# 5_AnalogChannels_1_2_3_4.net
KiCad netlist of a schematic drawn in Altium Designer
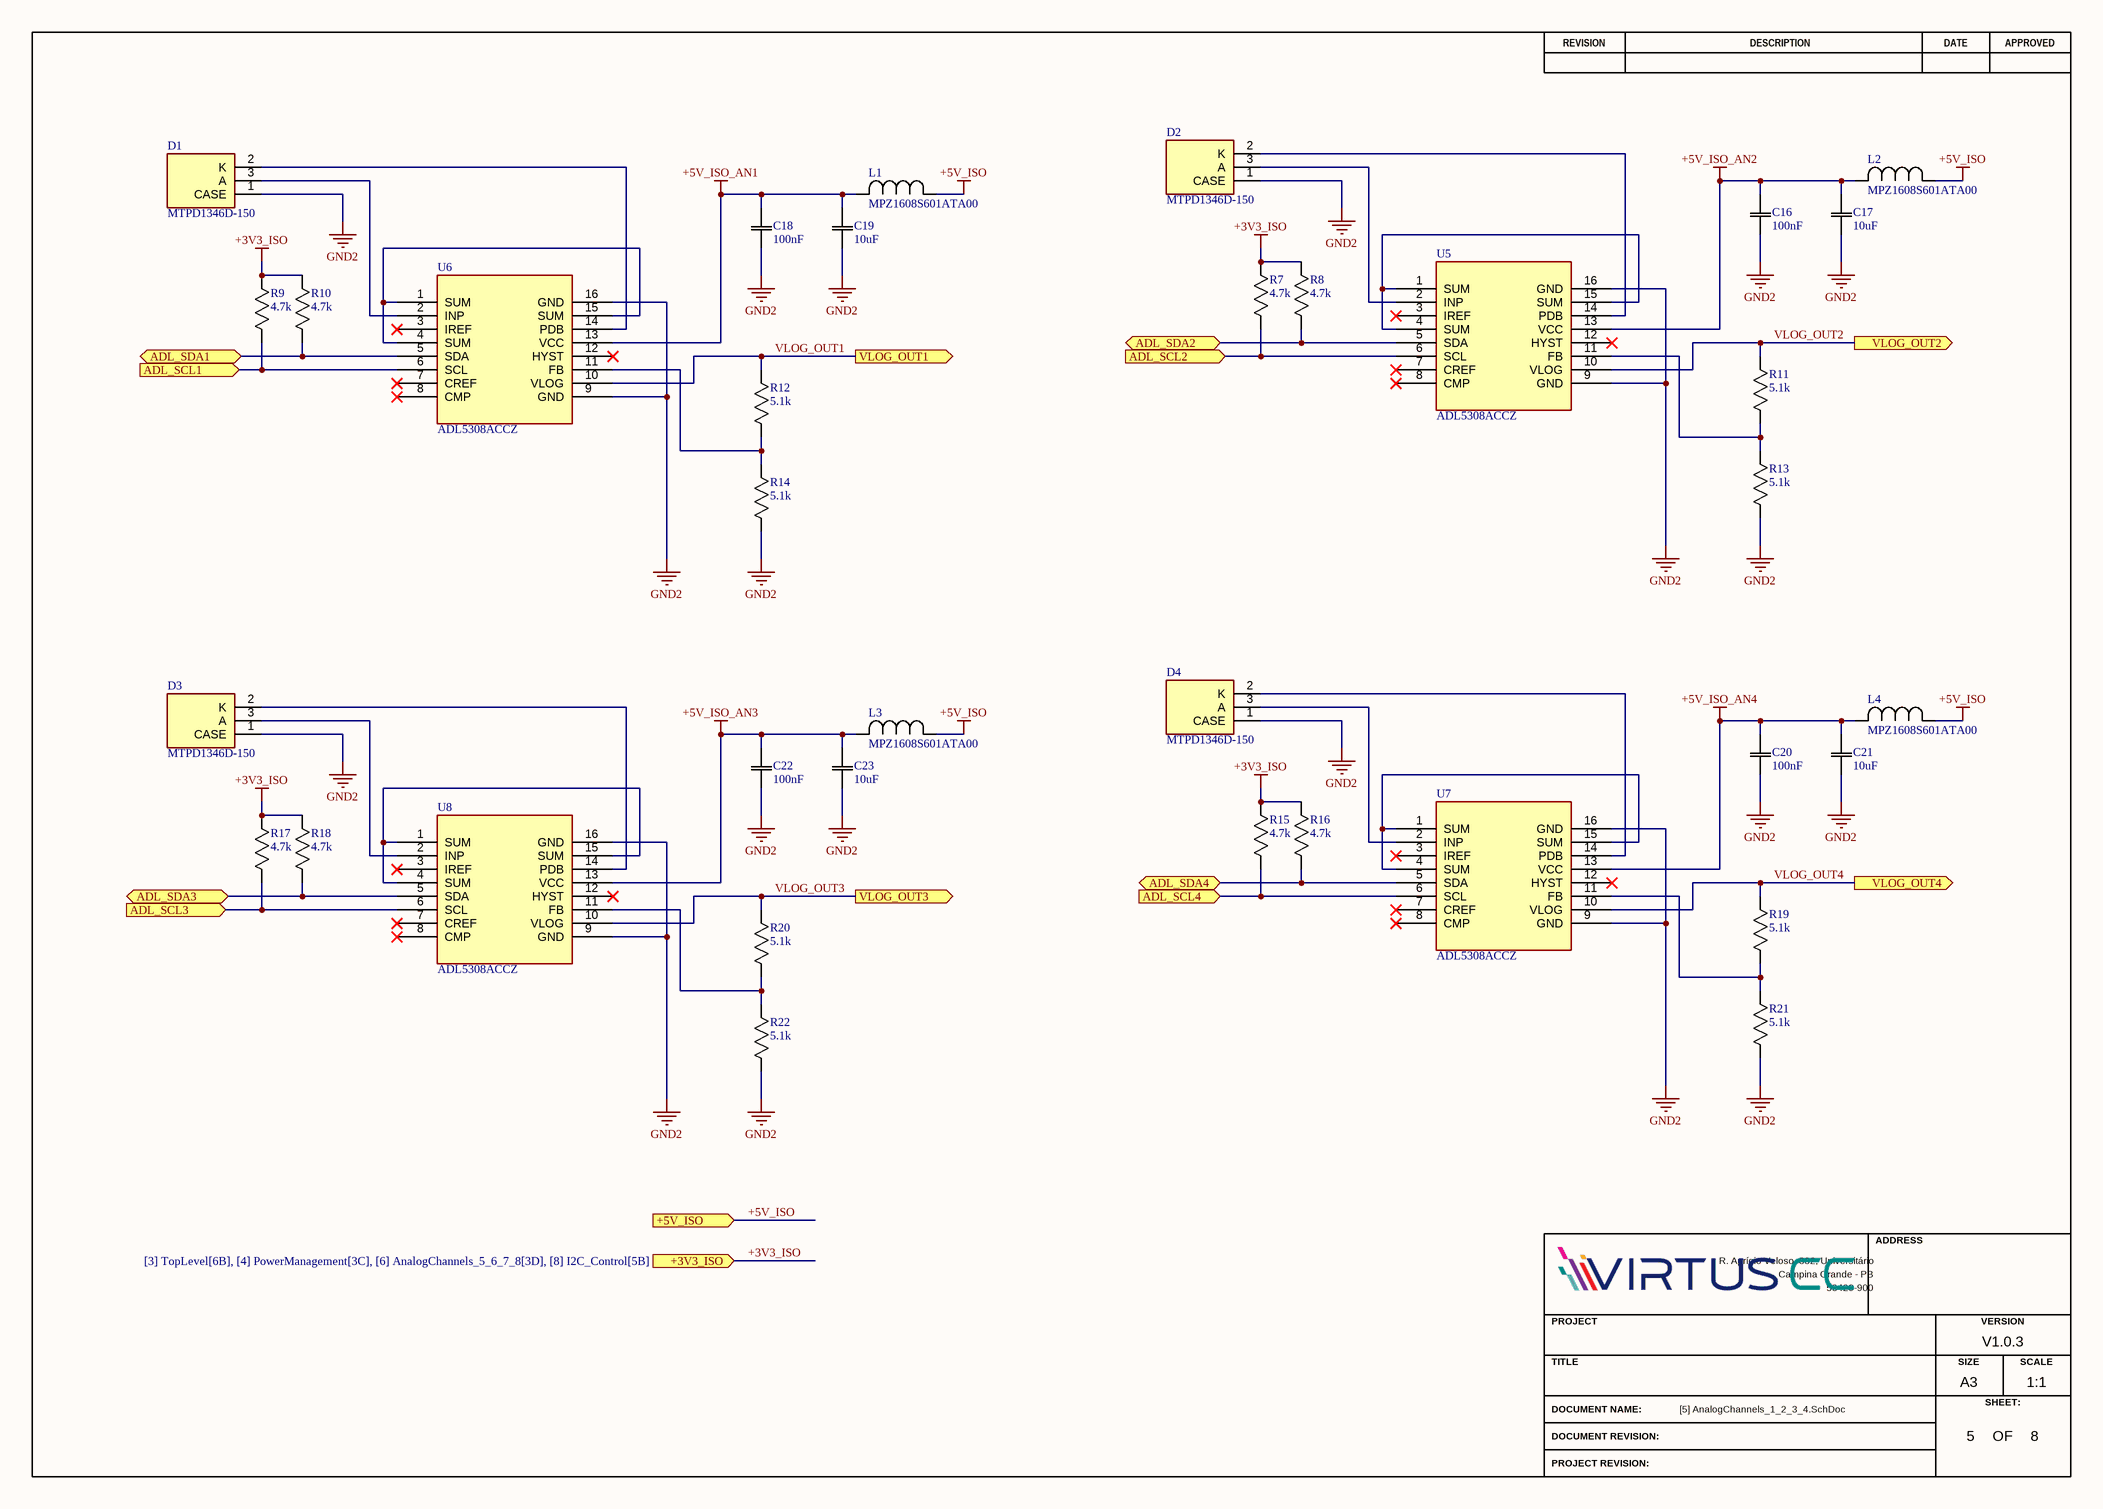
[diagram p0: [5] AnalogChannels_1_2_3_4.SchDoc]

(export (version "E")
  (design (tool "Eeschema 10.0.6"))
  (components
    (comp (ref "C16")
      (value "100nF")
      (footprint "CAPC1005X40N")
      (description "0.1 µF ±10% 50V Ceramic Capacitor X7R 0402 (1005 Metric)")
      (fields
        (field (name "MANUFACTURER_PART_NUMBER") "GCM155R71H104KE02D")
        (field (name "COPYRIGHT") "Copyright (C) 2026 Ultra Librarian. All rights reserved.")
      )
      (libsource (lib "PCEIOT") (part "GCM155R71H104KE02D"))
    )
    (comp (ref "C17")
      (value "10uF")
      (footprint "CAPC1005X40N")
      (description "10 µF ±20% 10V Ceramic Capacitor X5R 0402 (1005 Metric)")
      (fields
        (field (name "MANUFACTURER_PART_NUMBER") "GRT155R61A106ME13D")
        (field (name "COPYRIGHT") "Copyright (C) 2026 Ultra Librarian. All rights reserved.")
      )
      (libsource (lib "PCEIOT") (part "GRT155R61A106ME13D"))
    )
    (comp (ref "C18")
      (value "100nF")
      (footprint "CAPC1005X40N")
      (description "0.1 µF ±10% 50V Ceramic Capacitor X7R 0402 (1005 Metric)")
      (fields
        (field (name "MANUFACTURER_PART_NUMBER") "GCM155R71H104KE02D")
        (field (name "COPYRIGHT") "Copyright (C) 2026 Ultra Librarian. All rights reserved.")
      )
      (libsource (lib "PCEIOT") (part "GCM155R71H104KE02D"))
    )
    (comp (ref "C19")
      (value "10uF")
      (footprint "CAPC1005X40N")
      (description "10 µF ±20% 10V Ceramic Capacitor X5R 0402 (1005 Metric)")
      (fields
        (field (name "MANUFACTURER_PART_NUMBER") "GRT155R61A106ME13D")
        (field (name "COPYRIGHT") "Copyright (C) 2026 Ultra Librarian. All rights reserved.")
      )
      (libsource (lib "PCEIOT") (part "GRT155R61A106ME13D"))
    )
    (comp (ref "C20")
      (value "100nF")
      (footprint "CAPC1005X40N")
      (description "0.1 µF ±10% 50V Ceramic Capacitor X7R 0402 (1005 Metric)")
      (fields
        (field (name "MANUFACTURER_PART_NUMBER") "GCM155R71H104KE02D")
        (field (name "COPYRIGHT") "Copyright (C) 2026 Ultra Librarian. All rights reserved.")
      )
      (libsource (lib "PCEIOT") (part "GCM155R71H104KE02D"))
    )
    (comp (ref "C21")
      (value "10uF")
      (footprint "CAPC1005X40N")
      (description "10 µF ±20% 10V Ceramic Capacitor X5R 0402 (1005 Metric)")
      (fields
        (field (name "MANUFACTURER_PART_NUMBER") "GRT155R61A106ME13D")
        (field (name "COPYRIGHT") "Copyright (C) 2026 Ultra Librarian. All rights reserved.")
      )
      (libsource (lib "PCEIOT") (part "GRT155R61A106ME13D"))
    )
    (comp (ref "C22")
      (value "100nF")
      (footprint "CAPC1005X40N")
      (description "0.1 µF ±10% 50V Ceramic Capacitor X7R 0402 (1005 Metric)")
      (fields
        (field (name "MANUFACTURER_PART_NUMBER") "GCM155R71H104KE02D")
        (field (name "COPYRIGHT") "Copyright (C) 2026 Ultra Librarian. All rights reserved.")
      )
      (libsource (lib "PCEIOT") (part "GCM155R71H104KE02D"))
    )
    (comp (ref "C23")
      (value "10uF")
      (footprint "CAPC1005X40N")
      (description "10 µF ±20% 10V Ceramic Capacitor X5R 0402 (1005 Metric)")
      (fields
        (field (name "MANUFACTURER_PART_NUMBER") "GRT155R61A106ME13D")
        (field (name "COPYRIGHT") "Copyright (C) 2026 Ultra Librarian. All rights reserved.")
      )
      (libsource (lib "PCEIOT") (part "GRT155R61A106ME13D"))
    )
    (comp (ref "D1")
      (value "MTPD1346D-150")
      (footprint "TO127P540X1680-3N")
      (description "Photodiode 1300nm TO-46-3 Lens Top Metal Can")
      (libsource (lib "PCEIOT") (part "MTPD1346D-150"))
    )
    (comp (ref "D2")
      (value "MTPD1346D-150")
      (footprint "TO127P540X1680-3N")
      (description "Photodiode 1300nm TO-46-3 Lens Top Metal Can")
      (libsource (lib "PCEIOT") (part "MTPD1346D-150"))
    )
    (comp (ref "D3")
      (value "MTPD1346D-150")
      (footprint "TO127P540X1680-3N")
      (description "Photodiode 1300nm TO-46-3 Lens Top Metal Can")
      (libsource (lib "PCEIOT") (part "MTPD1346D-150"))
    )
    (comp (ref "D4")
      (value "MTPD1346D-150")
      (footprint "TO127P540X1680-3N")
      (description "Photodiode 1300nm TO-46-3 Lens Top Metal Can")
      (libsource (lib "PCEIOT") (part "MTPD1346D-150"))
    )
    (comp (ref "L1")
      (value "MPZ1608S601ATA00")
      (footprint "INDC1608X06N")
      (description "INDUCTOR; SMT (0603); FERRITE-BEAD; 600; TOL=+/-25%; 1A; -55 DEGC TO +125 DEGC")
      (fields (field (name "COPYRIGHT") "Copyright (C) 2026 Ultra Librarian. All rights reserved."))
      (libsource (lib "PCEIOT") (part "MPZ1608S601ATA00"))
    )
    (comp (ref "L2")
      (value "MPZ1608S601ATA00")
      (footprint "INDC1608X06N")
      (description "INDUCTOR; SMT (0603); FERRITE-BEAD; 600; TOL=+/-25%; 1A; -55 DEGC TO +125 DEGC")
      (fields (field (name "COPYRIGHT") "Copyright (C) 2026 Ultra Librarian. All rights reserved."))
      (libsource (lib "PCEIOT") (part "MPZ1608S601ATA00"))
    )
    (comp (ref "L3")
      (value "MPZ1608S601ATA00")
      (footprint "INDC1608X06N")
      (description "INDUCTOR; SMT (0603); FERRITE-BEAD; 600; TOL=+/-25%; 1A; -55 DEGC TO +125 DEGC")
      (fields (field (name "COPYRIGHT") "Copyright (C) 2026 Ultra Librarian. All rights reserved."))
      (libsource (lib "PCEIOT") (part "MPZ1608S601ATA00"))
    )
    (comp (ref "L4")
      (value "MPZ1608S601ATA00")
      (footprint "INDC1608X06N")
      (description "INDUCTOR; SMT (0603); FERRITE-BEAD; 600; TOL=+/-25%; 1A; -55 DEGC TO +125 DEGC")
      (fields (field (name "COPYRIGHT") "Copyright (C) 2026 Ultra Librarian. All rights reserved."))
      (libsource (lib "PCEIOT") (part "MPZ1608S601ATA00"))
    )
    (comp (ref "R7")
      (value "4.7k")
      (footprint "RESC1005X40N")
      (description "4.7 kOhms ±1% 0.063W, 1/16W Chip Resistor 0402 (1005 Metric) Moisture Resistant Thick Film")
      (fields
        (field (name "MANUFACTURER_PART_NUMBER") "RC0402FR-074K7L")
        (field (name "COPYRIGHT") "Copyright (C) 2025 Ultra Librarian. All rights reserved.")
      )
      (libsource (lib "PCEIOT") (part "RC0402FR-074K7L"))
    )
    (comp (ref "R8")
      (value "4.7k")
      (footprint "RESC1005X40N")
      (description "4.7 kOhms ±1% 0.063W, 1/16W Chip Resistor 0402 (1005 Metric) Moisture Resistant Thick Film")
      (fields
        (field (name "MANUFACTURER_PART_NUMBER") "RC0402FR-074K7L")
        (field (name "COPYRIGHT") "Copyright (C) 2025 Ultra Librarian. All rights reserved.")
      )
      (libsource (lib "PCEIOT") (part "RC0402FR-074K7L"))
    )
    (comp (ref "R9")
      (value "4.7k")
      (footprint "RESC1005X40N")
      (description "4.7 kOhms ±1% 0.063W, 1/16W Chip Resistor 0402 (1005 Metric) Moisture Resistant Thick Film")
      (fields
        (field (name "MANUFACTURER_PART_NUMBER") "RC0402FR-074K7L")
        (field (name "COPYRIGHT") "Copyright (C) 2025 Ultra Librarian. All rights reserved.")
      )
      (libsource (lib "PCEIOT") (part "RC0402FR-074K7L"))
    )
    (comp (ref "R10")
      (value "4.7k")
      (footprint "RESC1005X40N")
      (description "4.7 kOhms ±1% 0.063W, 1/16W Chip Resistor 0402 (1005 Metric) Moisture Resistant Thick Film")
      (fields
        (field (name "MANUFACTURER_PART_NUMBER") "RC0402FR-074K7L")
        (field (name "COPYRIGHT") "Copyright (C) 2025 Ultra Librarian. All rights reserved.")
      )
      (libsource (lib "PCEIOT") (part "RC0402FR-074K7L"))
    )
    (comp (ref "R11")
      (value "5.1k")
      (footprint "RESC1005X40N")
      (description "5.1 kOhms ±1% 0.063W, 1/16W Chip Resistor 0402 (1005 Metric) Moisture Resistant Thick Film")
      (fields
        (field (name "MANUFACTURER_PART_NUMBER") "RC0402FR-075K1L")
        (field (name "COPYRIGHT") "Copyright (C) 2025 Ultra Librarian. All rights reserved.")
      )
      (libsource (lib "PCEIOT") (part "RC0402FR-075K1L"))
    )
    (comp (ref "R12")
      (value "5.1k")
      (footprint "RESC1005X40N")
      (description "5.1 kOhms ±1% 0.063W, 1/16W Chip Resistor 0402 (1005 Metric) Moisture Resistant Thick Film")
      (fields
        (field (name "MANUFACTURER_PART_NUMBER") "RC0402FR-075K1L")
        (field (name "COPYRIGHT") "Copyright (C) 2025 Ultra Librarian. All rights reserved.")
      )
      (libsource (lib "PCEIOT") (part "RC0402FR-075K1L"))
    )
    (comp (ref "R13")
      (value "5.1k")
      (footprint "RESC1005X40N")
      (description "5.1 kOhms ±1% 0.063W, 1/16W Chip Resistor 0402 (1005 Metric) Moisture Resistant Thick Film")
      (fields
        (field (name "MANUFACTURER_PART_NUMBER") "RC0402FR-075K1L")
        (field (name "COPYRIGHT") "Copyright (C) 2025 Ultra Librarian. All rights reserved.")
      )
      (libsource (lib "PCEIOT") (part "RC0402FR-075K1L"))
    )
    (comp (ref "R14")
      (value "5.1k")
      (footprint "RESC1005X40N")
      (description "5.1 kOhms ±1% 0.063W, 1/16W Chip Resistor 0402 (1005 Metric) Moisture Resistant Thick Film")
      (fields
        (field (name "MANUFACTURER_PART_NUMBER") "RC0402FR-075K1L")
        (field (name "COPYRIGHT") "Copyright (C) 2025 Ultra Librarian. All rights reserved.")
      )
      (libsource (lib "PCEIOT") (part "RC0402FR-075K1L"))
    )
    (comp (ref "R15")
      (value "4.7k")
      (footprint "RESC1005X40N")
      (description "4.7 kOhms ±1% 0.063W, 1/16W Chip Resistor 0402 (1005 Metric) Moisture Resistant Thick Film")
      (fields
        (field (name "MANUFACTURER_PART_NUMBER") "RC0402FR-074K7L")
        (field (name "COPYRIGHT") "Copyright (C) 2025 Ultra Librarian. All rights reserved.")
      )
      (libsource (lib "PCEIOT") (part "RC0402FR-074K7L"))
    )
    (comp (ref "R16")
      (value "4.7k")
      (footprint "RESC1005X40N")
      (description "4.7 kOhms ±1% 0.063W, 1/16W Chip Resistor 0402 (1005 Metric) Moisture Resistant Thick Film")
      (fields
        (field (name "MANUFACTURER_PART_NUMBER") "RC0402FR-074K7L")
        (field (name "COPYRIGHT") "Copyright (C) 2025 Ultra Librarian. All rights reserved.")
      )
      (libsource (lib "PCEIOT") (part "RC0402FR-074K7L"))
    )
    (comp (ref "R17")
      (value "4.7k")
      (footprint "RESC1005X40N")
      (description "4.7 kOhms ±1% 0.063W, 1/16W Chip Resistor 0402 (1005 Metric) Moisture Resistant Thick Film")
      (fields
        (field (name "MANUFACTURER_PART_NUMBER") "RC0402FR-074K7L")
        (field (name "COPYRIGHT") "Copyright (C) 2025 Ultra Librarian. All rights reserved.")
      )
      (libsource (lib "PCEIOT") (part "RC0402FR-074K7L"))
    )
    (comp (ref "R18")
      (value "4.7k")
      (footprint "RESC1005X40N")
      (description "4.7 kOhms ±1% 0.063W, 1/16W Chip Resistor 0402 (1005 Metric) Moisture Resistant Thick Film")
      (fields
        (field (name "MANUFACTURER_PART_NUMBER") "RC0402FR-074K7L")
        (field (name "COPYRIGHT") "Copyright (C) 2025 Ultra Librarian. All rights reserved.")
      )
      (libsource (lib "PCEIOT") (part "RC0402FR-074K7L"))
    )
    (comp (ref "R19")
      (value "5.1k")
      (footprint "RESC1005X40N")
      (description "5.1 kOhms ±1% 0.063W, 1/16W Chip Resistor 0402 (1005 Metric) Moisture Resistant Thick Film")
      (fields
        (field (name "MANUFACTURER_PART_NUMBER") "RC0402FR-075K1L")
        (field (name "COPYRIGHT") "Copyright (C) 2025 Ultra Librarian. All rights reserved.")
      )
      (libsource (lib "PCEIOT") (part "RC0402FR-075K1L"))
    )
    (comp (ref "R20")
      (value "5.1k")
      (footprint "RESC1005X40N")
      (description "5.1 kOhms ±1% 0.063W, 1/16W Chip Resistor 0402 (1005 Metric) Moisture Resistant Thick Film")
      (fields
        (field (name "MANUFACTURER_PART_NUMBER") "RC0402FR-075K1L")
        (field (name "COPYRIGHT") "Copyright (C) 2025 Ultra Librarian. All rights reserved.")
      )
      (libsource (lib "PCEIOT") (part "RC0402FR-075K1L"))
    )
    (comp (ref "R21")
      (value "5.1k")
      (footprint "RESC1005X40N")
      (description "5.1 kOhms ±1% 0.063W, 1/16W Chip Resistor 0402 (1005 Metric) Moisture Resistant Thick Film")
      (fields
        (field (name "MANUFACTURER_PART_NUMBER") "RC0402FR-075K1L")
        (field (name "COPYRIGHT") "Copyright (C) 2025 Ultra Librarian. All rights reserved.")
      )
      (libsource (lib "PCEIOT") (part "RC0402FR-075K1L"))
    )
    (comp (ref "R22")
      (value "5.1k")
      (footprint "RESC1005X40N")
      (description "5.1 kOhms ±1% 0.063W, 1/16W Chip Resistor 0402 (1005 Metric) Moisture Resistant Thick Film")
      (fields
        (field (name "MANUFACTURER_PART_NUMBER") "RC0402FR-075K1L")
        (field (name "COPYRIGHT") "Copyright (C) 2025 Ultra Librarian. All rights reserved.")
      )
      (libsource (lib "PCEIOT") (part "RC0402FR-075K1L"))
    )
    (comp (ref "U5")
      (value "ADL5308ACCZ")
      (footprint "CC-14-4_ADI")
      (description "Logarithmic Converter, 105Deg C, Lga-Ep Rohs Compliant: Yes ¦Analog Devices, Inc. ADL5308ACCZ")
      (libsource (lib "PCEIOT") (part "ADL5308ACCZ"))
    )
    (comp (ref "U6")
      (value "ADL5308ACCZ")
      (footprint "CC-14-4_ADI")
      (description "Logarithmic Converter, 105Deg C, Lga-Ep Rohs Compliant: Yes ¦Analog Devices, Inc. ADL5308ACCZ")
      (libsource (lib "PCEIOT") (part "ADL5308ACCZ"))
    )
    (comp (ref "U7")
      (value "ADL5308ACCZ")
      (footprint "CC-14-4_ADI")
      (description "Logarithmic Converter, 105Deg C, Lga-Ep Rohs Compliant: Yes ¦Analog Devices, Inc. ADL5308ACCZ")
      (libsource (lib "PCEIOT") (part "ADL5308ACCZ"))
    )
    (comp (ref "U8")
      (value "ADL5308ACCZ")
      (footprint "CC-14-4_ADI")
      (description "Logarithmic Converter, 105Deg C, Lga-Ep Rohs Compliant: Yes ¦Analog Devices, Inc. ADL5308ACCZ")
      (libsource (lib "PCEIOT") (part "ADL5308ACCZ"))
    )
  )
  (nets
    (net (code "1") (name "+3V3_ISO") (class "Default")
      (node (ref "R10") (pin "1") (pinfunction "1_1") (pintype "passive"))
      (node (ref "R15") (pin "1") (pinfunction "1_1") (pintype "passive"))
      (node (ref "R16") (pin "1") (pinfunction "1_1") (pintype "passive"))
      (node (ref "R17") (pin "1") (pinfunction "1_1") (pintype "passive"))
      (node (ref "R18") (pin "1") (pinfunction "1_1") (pintype "passive"))
      (node (ref "R7") (pin "1") (pinfunction "1_1") (pintype "passive"))
      (node (ref "R8") (pin "1") (pinfunction "1_1") (pintype "passive"))
      (node (ref "R9") (pin "1") (pinfunction "1_1") (pintype "passive"))
    )
    (net (code "2") (name "+5V_ISO") (class "Default")
      (node (ref "L1") (pin "1") (pinfunction "1_1") (pintype "passive"))
      (node (ref "L2") (pin "1") (pinfunction "1_1") (pintype "passive"))
      (node (ref "L3") (pin "1") (pinfunction "1_1") (pintype "passive"))
      (node (ref "L4") (pin "1") (pinfunction "1_1") (pintype "passive"))
    )
    (net (code "3") (name "+5V_ISO_AN1") (class "Default")
      (node (ref "C18") (pin "2") (pinfunction "2_2") (pintype "passive"))
      (node (ref "C19") (pin "2") (pinfunction "2_2") (pintype "passive"))
      (node (ref "L1") (pin "2") (pinfunction "2_2") (pintype "passive"))
      (node (ref "U6") (pin "13") (pinfunction "VCC_13") (pintype "passive"))
    )
    (net (code "4") (name "+5V_ISO_AN2") (class "Default")
      (node (ref "C16") (pin "2") (pinfunction "2_2") (pintype "passive"))
      (node (ref "C17") (pin "2") (pinfunction "2_2") (pintype "passive"))
      (node (ref "L2") (pin "2") (pinfunction "2_2") (pintype "passive"))
      (node (ref "U5") (pin "13") (pinfunction "VCC_13") (pintype "passive"))
    )
    (net (code "5") (name "+5V_ISO_AN3") (class "Default")
      (node (ref "C22") (pin "2") (pinfunction "2_2") (pintype "passive"))
      (node (ref "C23") (pin "2") (pinfunction "2_2") (pintype "passive"))
      (node (ref "L3") (pin "2") (pinfunction "2_2") (pintype "passive"))
      (node (ref "U8") (pin "13") (pinfunction "VCC_13") (pintype "passive"))
    )
    (net (code "6") (name "+5V_ISO_AN4") (class "Default")
      (node (ref "C20") (pin "2") (pinfunction "2_2") (pintype "passive"))
      (node (ref "C21") (pin "2") (pinfunction "2_2") (pintype "passive"))
      (node (ref "L4") (pin "2") (pinfunction "2_2") (pintype "passive"))
      (node (ref "U7") (pin "13") (pinfunction "VCC_13") (pintype "passive"))
    )
    (net (code "7") (name "/ADL_SCL1") (class "Default")
      (node (ref "R9") (pin "2") (pinfunction "2_2") (pintype "passive"))
      (node (ref "U6") (pin "6") (pinfunction "SCL_6") (pintype "passive"))
    )
    (net (code "8") (name "/ADL_SCL2") (class "Default")
      (node (ref "R7") (pin "2") (pinfunction "2_2") (pintype "passive"))
      (node (ref "U5") (pin "6") (pinfunction "SCL_6") (pintype "passive"))
    )
    (net (code "9") (name "/ADL_SCL3") (class "Default")
      (node (ref "R17") (pin "2") (pinfunction "2_2") (pintype "passive"))
      (node (ref "U8") (pin "6") (pinfunction "SCL_6") (pintype "passive"))
    )
    (net (code "10") (name "/ADL_SCL4") (class "Default")
      (node (ref "R15") (pin "2") (pinfunction "2_2") (pintype "passive"))
      (node (ref "U7") (pin "6") (pinfunction "SCL_6") (pintype "passive"))
    )
    (net (code "11") (name "/ADL_SDA1") (class "Default")
      (node (ref "R10") (pin "2") (pinfunction "2_2") (pintype "passive"))
      (node (ref "U6") (pin "5") (pinfunction "SDA_5") (pintype "passive"))
    )
    (net (code "12") (name "/ADL_SDA2") (class "Default")
      (node (ref "R8") (pin "2") (pinfunction "2_2") (pintype "passive"))
      (node (ref "U5") (pin "5") (pinfunction "SDA_5") (pintype "passive"))
    )
    (net (code "13") (name "/ADL_SDA3") (class "Default")
      (node (ref "R18") (pin "2") (pinfunction "2_2") (pintype "passive"))
      (node (ref "U8") (pin "5") (pinfunction "SDA_5") (pintype "passive"))
    )
    (net (code "14") (name "/ADL_SDA4") (class "Default")
      (node (ref "R16") (pin "2") (pinfunction "2_2") (pintype "passive"))
      (node (ref "U7") (pin "5") (pinfunction "SDA_5") (pintype "passive"))
    )
    (net (code "15") (name "/VLOG_OUT1") (class "Default")
      (node (ref "R12") (pin "1") (pinfunction "1_1") (pintype "passive"))
      (node (ref "U6") (pin "10") (pinfunction "VLOG_10") (pintype "passive"))
    )
    (net (code "16") (name "/VLOG_OUT2") (class "Default")
      (node (ref "R11") (pin "1") (pinfunction "1_1") (pintype "passive"))
      (node (ref "U5") (pin "10") (pinfunction "VLOG_10") (pintype "passive"))
    )
    (net (code "17") (name "/VLOG_OUT3") (class "Default")
      (node (ref "R20") (pin "1") (pinfunction "1_1") (pintype "passive"))
      (node (ref "U8") (pin "10") (pinfunction "VLOG_10") (pintype "passive"))
    )
    (net (code "18") (name "/VLOG_OUT4") (class "Default")
      (node (ref "R19") (pin "1") (pinfunction "1_1") (pintype "passive"))
      (node (ref "U7") (pin "10") (pinfunction "VLOG_10") (pintype "passive"))
    )
    (net (code "19") (name "GND2") (class "Default")
      (node (ref "C16") (pin "1") (pinfunction "1_1") (pintype "passive"))
      (node (ref "C17") (pin "1") (pinfunction "1_1") (pintype "passive"))
      (node (ref "C18") (pin "1") (pinfunction "1_1") (pintype "passive"))
      (node (ref "C19") (pin "1") (pinfunction "1_1") (pintype "passive"))
      (node (ref "C20") (pin "1") (pinfunction "1_1") (pintype "passive"))
      (node (ref "C21") (pin "1") (pinfunction "1_1") (pintype "passive"))
      (node (ref "C22") (pin "1") (pinfunction "1_1") (pintype "passive"))
      (node (ref "C23") (pin "1") (pinfunction "1_1") (pintype "passive"))
      (node (ref "D1") (pin "1") (pinfunction "CASE_1") (pintype "passive"))
      (node (ref "D2") (pin "1") (pinfunction "CASE_1") (pintype "passive"))
      (node (ref "D3") (pin "1") (pinfunction "CASE_1") (pintype "passive"))
      (node (ref "D4") (pin "1") (pinfunction "CASE_1") (pintype "passive"))
      (node (ref "R13") (pin "2") (pinfunction "2_2") (pintype "passive"))
      (node (ref "R14") (pin "2") (pinfunction "2_2") (pintype "passive"))
      (node (ref "R21") (pin "2") (pinfunction "2_2") (pintype "passive"))
      (node (ref "R22") (pin "2") (pinfunction "2_2") (pintype "passive"))
      (node (ref "U5") (pin "16") (pinfunction "GND_16") (pintype "passive"))
      (node (ref "U5") (pin "9") (pinfunction "GND_9") (pintype "passive"))
      (node (ref "U6") (pin "16") (pinfunction "GND_16") (pintype "passive"))
      (node (ref "U6") (pin "9") (pinfunction "GND_9") (pintype "passive"))
      (node (ref "U7") (pin "16") (pinfunction "GND_16") (pintype "passive"))
      (node (ref "U7") (pin "9") (pinfunction "GND_9") (pintype "passive"))
      (node (ref "U8") (pin "16") (pinfunction "GND_16") (pintype "passive"))
      (node (ref "U8") (pin "9") (pinfunction "GND_9") (pintype "passive"))
    )
    (net (code "20") (name "Net-(D1-A)") (class "Default")
      (node (ref "D1") (pin "3") (pinfunction "A_3") (pintype "passive"))
      (node (ref "U6") (pin "2") (pinfunction "INP_2") (pintype "passive"))
    )
    (net (code "21") (name "Net-(D1-K)") (class "Default")
      (node (ref "D1") (pin "2") (pinfunction "K_2") (pintype "passive"))
      (node (ref "U6") (pin "14") (pinfunction "PDB_14") (pintype "passive"))
    )
    (net (code "22") (name "Net-(D2-A)") (class "Default")
      (node (ref "D2") (pin "3") (pinfunction "A_3") (pintype "passive"))
      (node (ref "U5") (pin "2") (pinfunction "INP_2") (pintype "passive"))
    )
    (net (code "23") (name "Net-(D2-K)") (class "Default")
      (node (ref "D2") (pin "2") (pinfunction "K_2") (pintype "passive"))
      (node (ref "U5") (pin "14") (pinfunction "PDB_14") (pintype "passive"))
    )
    (net (code "24") (name "Net-(D3-A)") (class "Default")
      (node (ref "D3") (pin "3") (pinfunction "A_3") (pintype "passive"))
      (node (ref "U8") (pin "2") (pinfunction "INP_2") (pintype "passive"))
    )
    (net (code "25") (name "Net-(D3-K)") (class "Default")
      (node (ref "D3") (pin "2") (pinfunction "K_2") (pintype "passive"))
      (node (ref "U8") (pin "14") (pinfunction "PDB_14") (pintype "passive"))
    )
    (net (code "26") (name "Net-(D4-A)") (class "Default")
      (node (ref "D4") (pin "3") (pinfunction "A_3") (pintype "passive"))
      (node (ref "U7") (pin "2") (pinfunction "INP_2") (pintype "passive"))
    )
    (net (code "27") (name "Net-(D4-K)") (class "Default")
      (node (ref "D4") (pin "2") (pinfunction "K_2") (pintype "passive"))
      (node (ref "U7") (pin "14") (pinfunction "PDB_14") (pintype "passive"))
    )
    (net (code "28") (name "Net-(U5-FB)") (class "Default")
      (node (ref "R11") (pin "2") (pinfunction "2_2") (pintype "passive"))
      (node (ref "R13") (pin "1") (pinfunction "1_1") (pintype "passive"))
      (node (ref "U5") (pin "11") (pinfunction "FB_11") (pintype "passive"))
    )
    (net (code "29") (name "Net-(U5-SUM-Pad1)") (class "Default")
      (node (ref "U5") (pin "1") (pinfunction "SUM_1") (pintype "passive"))
      (node (ref "U5") (pin "15") (pinfunction "SUM_15") (pintype "passive"))
      (node (ref "U5") (pin "4") (pinfunction "SUM_4") (pintype "passive"))
    )
    (net (code "30") (name "Net-(U6-FB)") (class "Default")
      (node (ref "R12") (pin "2") (pinfunction "2_2") (pintype "passive"))
      (node (ref "R14") (pin "1") (pinfunction "1_1") (pintype "passive"))
      (node (ref "U6") (pin "11") (pinfunction "FB_11") (pintype "passive"))
    )
    (net (code "31") (name "Net-(U6-SUM-Pad1)") (class "Default")
      (node (ref "U6") (pin "1") (pinfunction "SUM_1") (pintype "passive"))
      (node (ref "U6") (pin "15") (pinfunction "SUM_15") (pintype "passive"))
      (node (ref "U6") (pin "4") (pinfunction "SUM_4") (pintype "passive"))
    )
    (net (code "32") (name "Net-(U7-FB)") (class "Default")
      (node (ref "R19") (pin "2") (pinfunction "2_2") (pintype "passive"))
      (node (ref "R21") (pin "1") (pinfunction "1_1") (pintype "passive"))
      (node (ref "U7") (pin "11") (pinfunction "FB_11") (pintype "passive"))
    )
    (net (code "33") (name "Net-(U7-SUM-Pad1)") (class "Default")
      (node (ref "U7") (pin "1") (pinfunction "SUM_1") (pintype "passive"))
      (node (ref "U7") (pin "15") (pinfunction "SUM_15") (pintype "passive"))
      (node (ref "U7") (pin "4") (pinfunction "SUM_4") (pintype "passive"))
    )
    (net (code "34") (name "Net-(U8-FB)") (class "Default")
      (node (ref "R20") (pin "2") (pinfunction "2_2") (pintype "passive"))
      (node (ref "R22") (pin "1") (pinfunction "1_1") (pintype "passive"))
      (node (ref "U8") (pin "11") (pinfunction "FB_11") (pintype "passive"))
    )
    (net (code "35") (name "Net-(U8-SUM-Pad1)") (class "Default")
      (node (ref "U8") (pin "1") (pinfunction "SUM_1") (pintype "passive"))
      (node (ref "U8") (pin "15") (pinfunction "SUM_15") (pintype "passive"))
      (node (ref "U8") (pin "4") (pinfunction "SUM_4") (pintype "passive"))
    )
    (net (code "36") (name "unconnected-(U5-CMP-Pad8)") (class "Default")
      (node (ref "U5") (pin "8") (pinfunction "CMP_8") (pintype "passive+no_connect"))
    )
    (net (code "37") (name "unconnected-(U5-CREF-Pad7)") (class "Default")
      (node (ref "U5") (pin "7") (pinfunction "CREF_7") (pintype "passive+no_connect"))
    )
    (net (code "38") (name "unconnected-(U5-HYST-Pad12)") (class "Default")
      (node (ref "U5") (pin "12") (pinfunction "HYST_12") (pintype "passive+no_connect"))
    )
    (net (code "39") (name "unconnected-(U5-IREF-Pad3)") (class "Default")
      (node (ref "U5") (pin "3") (pinfunction "IREF_3") (pintype "passive+no_connect"))
    )
    (net (code "40") (name "unconnected-(U6-CMP-Pad8)") (class "Default")
      (node (ref "U6") (pin "8") (pinfunction "CMP_8") (pintype "passive+no_connect"))
    )
    (net (code "41") (name "unconnected-(U6-CREF-Pad7)") (class "Default")
      (node (ref "U6") (pin "7") (pinfunction "CREF_7") (pintype "passive+no_connect"))
    )
    (net (code "42") (name "unconnected-(U6-HYST-Pad12)") (class "Default")
      (node (ref "U6") (pin "12") (pinfunction "HYST_12") (pintype "passive+no_connect"))
    )
    (net (code "43") (name "unconnected-(U6-IREF-Pad3)") (class "Default")
      (node (ref "U6") (pin "3") (pinfunction "IREF_3") (pintype "passive+no_connect"))
    )
    (net (code "44") (name "unconnected-(U7-CMP-Pad8)") (class "Default")
      (node (ref "U7") (pin "8") (pinfunction "CMP_8") (pintype "passive+no_connect"))
    )
    (net (code "45") (name "unconnected-(U7-CREF-Pad7)") (class "Default")
      (node (ref "U7") (pin "7") (pinfunction "CREF_7") (pintype "passive+no_connect"))
    )
    (net (code "46") (name "unconnected-(U7-HYST-Pad12)") (class "Default")
      (node (ref "U7") (pin "12") (pinfunction "HYST_12") (pintype "passive+no_connect"))
    )
    (net (code "47") (name "unconnected-(U7-IREF-Pad3)") (class "Default")
      (node (ref "U7") (pin "3") (pinfunction "IREF_3") (pintype "passive+no_connect"))
    )
    (net (code "48") (name "unconnected-(U8-CMP-Pad8)") (class "Default")
      (node (ref "U8") (pin "8") (pinfunction "CMP_8") (pintype "passive+no_connect"))
    )
    (net (code "49") (name "unconnected-(U8-CREF-Pad7)") (class "Default")
      (node (ref "U8") (pin "7") (pinfunction "CREF_7") (pintype "passive+no_connect"))
    )
    (net (code "50") (name "unconnected-(U8-HYST-Pad12)") (class "Default")
      (node (ref "U8") (pin "12") (pinfunction "HYST_12") (pintype "passive+no_connect"))
    )
    (net (code "51") (name "unconnected-(U8-IREF-Pad3)") (class "Default")
      (node (ref "U8") (pin "3") (pinfunction "IREF_3") (pintype "passive+no_connect"))
    )
  )
)
